# minimal-arduino-uno-rev3-02-th.net
KiCad netlist of a schematic drawn in EAGLE
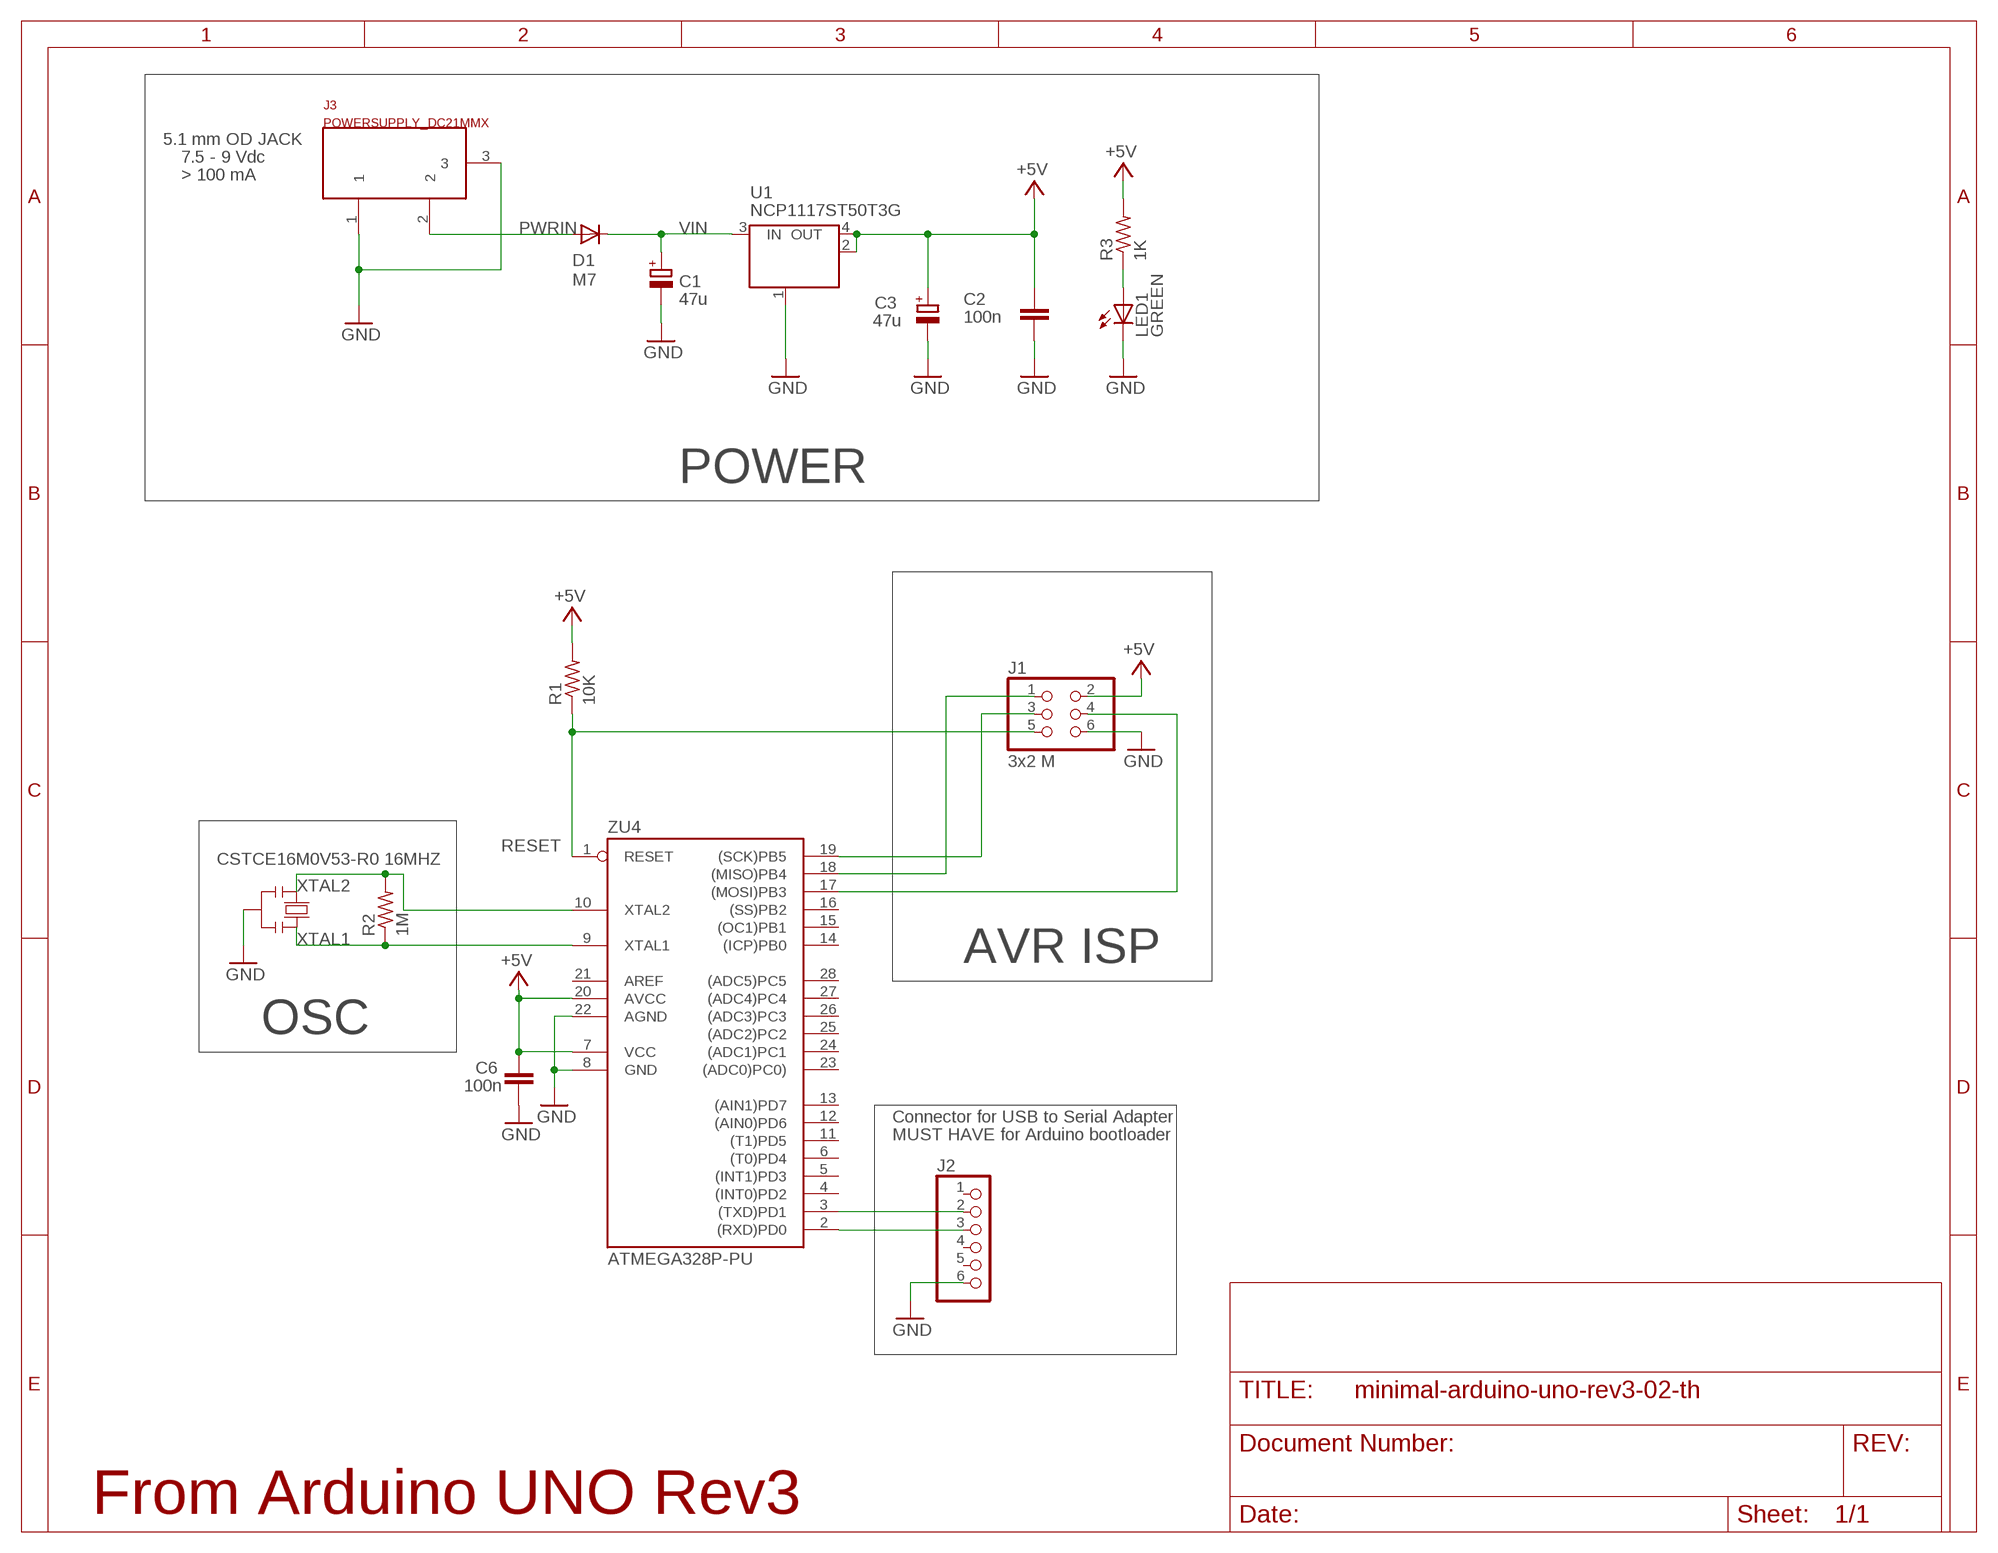
[diagram p0: schematic, sheet 1]

(export (version "E")
  (design (tool "Eeschema 10.0.6"))
  (components
    (comp (ref "C1")
      (value "47u")
      (footprint "eagle-import:PANASONIC_D")
      (libsource (lib "eagle-import") (part "CPOL-EUD"))
    )
    (comp (ref "C2")
      (value "100n")
      (footprint "eagle-import:C0805")
      (libsource (lib "eagle-import") (part "C-EUC0805"))
    )
    (comp (ref "C3")
      (value "47u")
      (footprint "eagle-import:PANASONIC_D")
      (libsource (lib "eagle-import") (part "CPOL-EUD"))
    )
    (comp (ref "C6")
      (value "100n")
      (footprint "eagle-import:C0805")
      (libsource (lib "eagle-import") (part "C-EUC0805"))
    )
    (comp (ref "D1")
      (value "M7")
      (footprint "eagle-import:SMB")
      (libsource (lib "eagle-import") (part "DIODE-SMB"))
    )
    (comp (ref "J1")
      (value "3x2 M")
      (footprint "eagle-import:2X03")
      (libsource (lib "eagle-import") (part "PINHD-2X3"))
    )
    (comp (ref "J2")
      (value "PINHD-1X6")
      (footprint "eagle-import:1X06")
      (libsource (lib "eagle-import") (part "PINHD-1X6"))
    )
    (comp (ref "J3")
      (value "POWERSUPPLY_DC21MMX")
      (footprint "eagle-import:POWERSUPPLY_DC-21MM")
      (libsource (lib "eagle-import") (part "POWERSUPPLY_DC21MMX"))
    )
    (comp (ref "LED1")
      (value "GREEN")
      (footprint "eagle-import:CHIP-LED0805")
      (libsource (lib "eagle-import") (part "LEDCHIP-LED0805"))
    )
    (comp (ref "R1")
      (value "10K")
      (footprint "eagle-import:R0805")
      (libsource (lib "eagle-import") (part "R-US_R0805"))
    )
    (comp (ref "R2")
      (value "1M")
      (footprint "eagle-import:R0805")
      (libsource (lib "eagle-import") (part "R-US_R0805"))
    )
    (comp (ref "R3")
      (value "1K")
      (footprint "eagle-import:R0805")
      (libsource (lib "eagle-import") (part "R-US_R0805"))
    )
    (comp (ref "U1")
      (value "NCP1117ST50T3G")
      (footprint "eagle-import:SOT223")
      (libsource (lib "eagle-import") (part "MC33269ST-3.3T3"))
    )
    (comp (ref "X1")
      (value "CSTCE16M0V53-R0 16MHZ")
      (footprint "eagle-import:RESONATOR")
      (libsource (lib "eagle-import") (part "RESONATORMU"))
    )
    (comp (ref "ZU4")
      (value "ATMEGA328P-PU")
      (footprint "eagle-import:DIL28-3")
      (libsource (lib "eagle-import") (part "ATMEGA328P-PU"))
    )
  )
  (nets
    (net (code "1") (name "+5V") (class "Default")
      (node (ref "C2") (pin "2") (pinfunction "2_2") (pintype "passive"))
      (node (ref "C3") (pin "+") (pinfunction "+_+") (pintype "passive"))
      (node (ref "C6") (pin "2") (pinfunction "2_2") (pintype "passive"))
      (node (ref "J1") (pin "2") (pinfunction "2_2") (pintype "passive"))
      (node (ref "R1") (pin "2") (pinfunction "2_2") (pintype "passive"))
      (node (ref "R3") (pin "2") (pinfunction "2_2") (pintype "passive"))
      (node (ref "U1") (pin "2") (pinfunction "OUT_2") (pintype "passive"))
      (node (ref "U1") (pin "4") (pinfunction "OUT_4") (pintype "passive"))
      (node (ref "ZU4") (pin "20") (pinfunction "AVCC_20") (pintype "power_in"))
      (node (ref "ZU4") (pin "7") (pinfunction "VCC_7") (pintype "power_in"))
    )
    (net (code "2") (name "/PWRIN") (class "Default")
      (node (ref "D1") (pin "A") (pinfunction "A_A") (pintype "passive"))
      (node (ref "J3") (pin "2") (pinfunction "2_2") (pintype "power_in"))
    )
    (net (code "3") (name "/RESET") (class "Default")
      (node (ref "J1") (pin "5") (pinfunction "5_5") (pintype "passive"))
      (node (ref "R1") (pin "1") (pinfunction "1_1") (pintype "passive"))
      (node (ref "ZU4") (pin "1") (pinfunction "RESET_1") (pintype "input"))
    )
    (net (code "4") (name "/VIN") (class "Default")
      (node (ref "C1") (pin "+") (pinfunction "+_+") (pintype "passive"))
      (node (ref "D1") (pin "C") (pinfunction "C_C") (pintype "passive"))
      (node (ref "U1") (pin "3") (pinfunction "IN_3") (pintype "input"))
    )
    (net (code "5") (name "/XTAL1") (class "Default")
      (node (ref "R2") (pin "1") (pinfunction "1_1") (pintype "passive"))
      (node (ref "X1") (pin "3") (pinfunction "3_3") (pintype "passive"))
      (node (ref "ZU4") (pin "9") (pinfunction "XTAL1_9") (pintype "bidirectional"))
    )
    (net (code "6") (name "/XTAL2") (class "Default")
      (node (ref "R2") (pin "2") (pinfunction "2_2") (pintype "passive"))
      (node (ref "X1") (pin "1") (pinfunction "1_1") (pintype "passive"))
      (node (ref "ZU4") (pin "10") (pinfunction "XTAL2_10") (pintype "bidirectional"))
    )
    (net (code "7") (name "GND") (class "Default")
      (node (ref "C1") (pin "-") (pinfunction "-_-") (pintype "passive"))
      (node (ref "C2") (pin "1") (pinfunction "1_1") (pintype "passive"))
      (node (ref "C3") (pin "-") (pinfunction "-_-") (pintype "passive"))
      (node (ref "C6") (pin "1") (pinfunction "1_1") (pintype "passive"))
      (node (ref "J1") (pin "6") (pinfunction "6_6") (pintype "passive"))
      (node (ref "J2") (pin "6") (pinfunction "6_6") (pintype "passive"))
      (node (ref "J3") (pin "1") (pinfunction "1_1") (pintype "power_in"))
      (node (ref "J3") (pin "3") (pinfunction "3_3") (pintype "power_in"))
      (node (ref "LED1") (pin "C") (pinfunction "C_C") (pintype "passive"))
      (node (ref "U1") (pin "1") (pinfunction "GND/ADJ_1") (pintype "input"))
      (node (ref "X1") (pin "2") (pinfunction "2_2") (pintype "passive"))
      (node (ref "ZU4") (pin "22") (pinfunction "AGND_22") (pintype "power_in"))
      (node (ref "ZU4") (pin "8") (pinfunction "GND_8") (pintype "power_in"))
    )
    (net (code "8") (name "Net-(LED1-PadA)") (class "Default")
      (node (ref "LED1") (pin "A") (pinfunction "A_A") (pintype "passive"))
      (node (ref "R3") (pin "1") (pinfunction "1_1") (pintype "passive"))
    )
    (net (code "9") (name "Net-(ZU4-(MISO)PB4)") (class "Default")
      (node (ref "J1") (pin "1") (pinfunction "1_1") (pintype "passive"))
      (node (ref "ZU4") (pin "18") (pinfunction "(MISO)PB4_18") (pintype "bidirectional"))
    )
    (net (code "10") (name "Net-(ZU4-(MOSI)PB3)") (class "Default")
      (node (ref "J1") (pin "4") (pinfunction "4_4") (pintype "passive"))
      (node (ref "ZU4") (pin "17") (pinfunction "(MOSI)PB3_17") (pintype "bidirectional"))
    )
    (net (code "11") (name "Net-(ZU4-(RXD)PD0)") (class "Default")
      (node (ref "J2") (pin "3") (pinfunction "3_3") (pintype "passive"))
      (node (ref "ZU4") (pin "2") (pinfunction "(RXD)PD0_2") (pintype "bidirectional"))
    )
    (net (code "12") (name "Net-(ZU4-(SCK)PB5)") (class "Default")
      (node (ref "J1") (pin "3") (pinfunction "3_3") (pintype "passive"))
      (node (ref "ZU4") (pin "19") (pinfunction "(SCK)PB5_19") (pintype "bidirectional"))
    )
    (net (code "13") (name "Net-(ZU4-(TXD)PD1)") (class "Default")
      (node (ref "J2") (pin "2") (pinfunction "2_2") (pintype "passive"))
      (node (ref "ZU4") (pin "3") (pinfunction "(TXD)PD1_3") (pintype "bidirectional"))
    )
    (net (code "14") (name "unconnected-(J2-Pad1)") (class "Default")
      (node (ref "J2") (pin "1") (pinfunction "1_1") (pintype "passive"))
    )
    (net (code "15") (name "unconnected-(J2-Pad4)") (class "Default")
      (node (ref "J2") (pin "4") (pinfunction "4_4") (pintype "passive"))
    )
    (net (code "16") (name "unconnected-(J2-Pad5)") (class "Default")
      (node (ref "J2") (pin "5") (pinfunction "5_5") (pintype "passive"))
    )
    (net (code "17") (name "unconnected-(ZU4-(ADC0)PC0)-Pad23)") (class "Default")
      (node (ref "ZU4") (pin "23") (pinfunction "(ADC0)PC0)_23") (pintype "bidirectional"))
    )
    (net (code "18") (name "unconnected-(ZU4-(ADC1)PC1-Pad24)") (class "Default")
      (node (ref "ZU4") (pin "24") (pinfunction "(ADC1)PC1_24") (pintype "bidirectional"))
    )
    (net (code "19") (name "unconnected-(ZU4-(ADC2)PC2-Pad25)") (class "Default")
      (node (ref "ZU4") (pin "25") (pinfunction "(ADC2)PC2_25") (pintype "bidirectional"))
    )
    (net (code "20") (name "unconnected-(ZU4-(ADC3)PC3-Pad26)") (class "Default")
      (node (ref "ZU4") (pin "26") (pinfunction "(ADC3)PC3_26") (pintype "bidirectional"))
    )
    (net (code "21") (name "unconnected-(ZU4-(ADC4)PC4-Pad27)") (class "Default")
      (node (ref "ZU4") (pin "27") (pinfunction "(ADC4)PC4_27") (pintype "bidirectional"))
    )
    (net (code "22") (name "unconnected-(ZU4-(ADC5)PC5-Pad28)") (class "Default")
      (node (ref "ZU4") (pin "28") (pinfunction "(ADC5)PC5_28") (pintype "bidirectional"))
    )
    (net (code "23") (name "unconnected-(ZU4-(AIN0)PD6-Pad12)") (class "Default")
      (node (ref "ZU4") (pin "12") (pinfunction "(AIN0)PD6_12") (pintype "bidirectional"))
    )
    (net (code "24") (name "unconnected-(ZU4-(AIN1)PD7-Pad13)") (class "Default")
      (node (ref "ZU4") (pin "13") (pinfunction "(AIN1)PD7_13") (pintype "bidirectional"))
    )
    (net (code "25") (name "unconnected-(ZU4-(ICP)PB0-Pad14)") (class "Default")
      (node (ref "ZU4") (pin "14") (pinfunction "(ICP)PB0_14") (pintype "bidirectional"))
    )
    (net (code "26") (name "unconnected-(ZU4-(INT0)PD2-Pad4)") (class "Default")
      (node (ref "ZU4") (pin "4") (pinfunction "(INT0)PD2_4") (pintype "bidirectional"))
    )
    (net (code "27") (name "unconnected-(ZU4-(INT1)PD3-Pad5)") (class "Default")
      (node (ref "ZU4") (pin "5") (pinfunction "(INT1)PD3_5") (pintype "bidirectional"))
    )
    (net (code "28") (name "unconnected-(ZU4-(OC1)PB1-Pad15)") (class "Default")
      (node (ref "ZU4") (pin "15") (pinfunction "(OC1)PB1_15") (pintype "bidirectional"))
    )
    (net (code "29") (name "unconnected-(ZU4-(SS)PB2-Pad16)") (class "Default")
      (node (ref "ZU4") (pin "16") (pinfunction "(SS)PB2_16") (pintype "bidirectional"))
    )
    (net (code "30") (name "unconnected-(ZU4-(T0)PD4-Pad6)") (class "Default")
      (node (ref "ZU4") (pin "6") (pinfunction "(T0)PD4_6") (pintype "bidirectional"))
    )
    (net (code "31") (name "unconnected-(ZU4-(T1)PD5-Pad11)") (class "Default")
      (node (ref "ZU4") (pin "11") (pinfunction "(T1)PD5_11") (pintype "bidirectional"))
    )
    (net (code "32") (name "unconnected-(ZU4-AREF-Pad21)") (class "Default")
      (node (ref "ZU4") (pin "21") (pinfunction "AREF_21") (pintype "passive"))
    )
  )
)
